# Own_21700_Board_v2_0_Final_AR.net
KiCad netlist of a schematic drawn in EAGLE
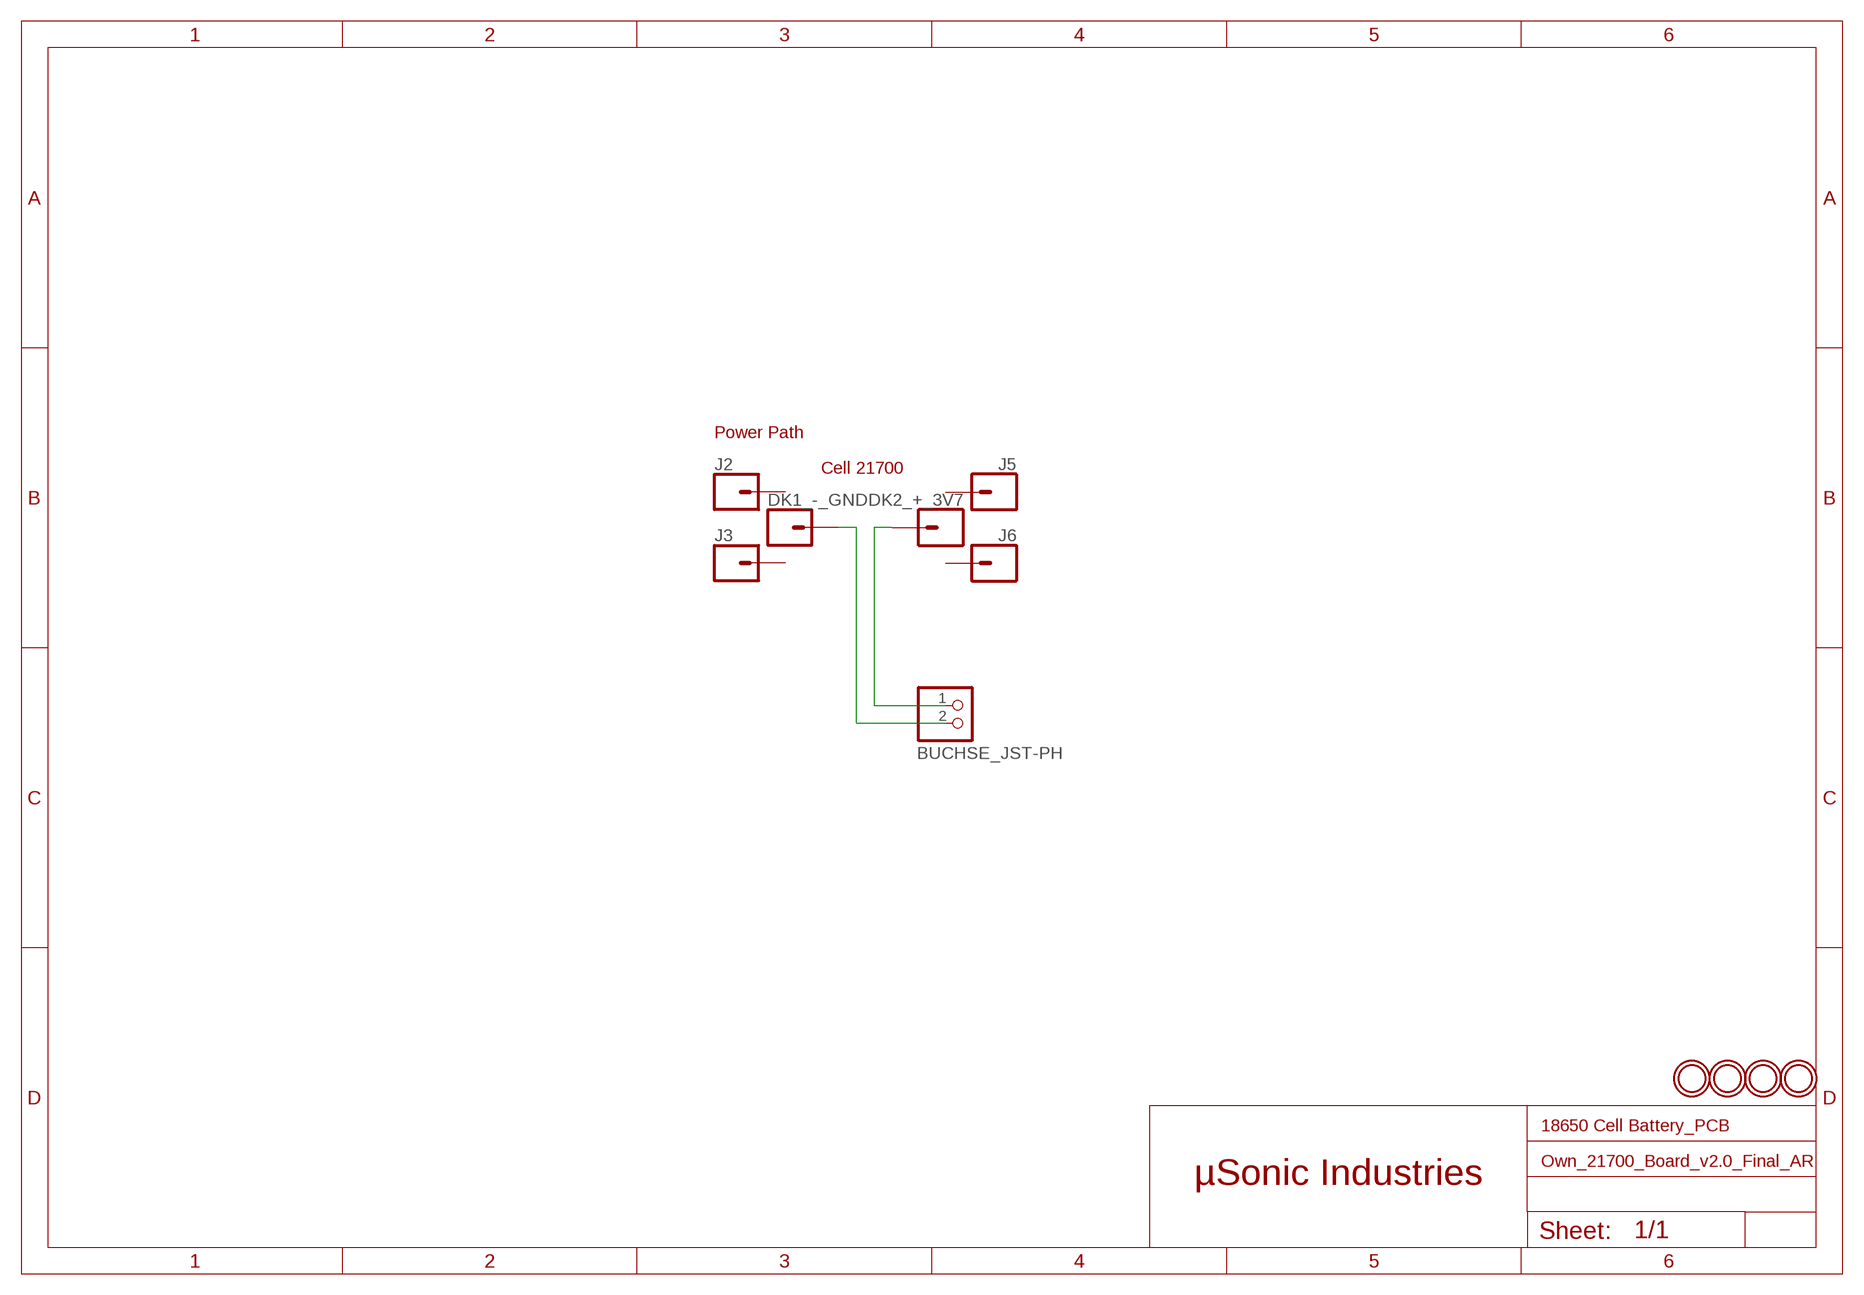
[diagram p0: schematic, sheet 1]

(export (version "E")
  (design (tool "Eeschema 10.0.6"))
  (components
    (comp (ref "BUCHSE_JST-PH")
      (value "JST_2PINOWN")
      (footprint "eagle-import:JST-PH-2-THMOWN")
      (libsource (lib "eagle-import") (part "JST_2PINOWN"))
    )
    (comp (ref "DK1_-_GND")
      (value "CONN_01PTH_2MM")
      (footprint "eagle-import:1X01_2MM")
      (libsource (lib "eagle-import") (part "CONN_01PTH_2MM"))
    )
    (comp (ref "DK2_+_3V7")
      (value "CONN_01PTH_2MM")
      (footprint "eagle-import:1X01_2MM")
      (libsource (lib "eagle-import") (part "CONN_01PTH_2MM"))
    )
    (comp (ref "J2")
      (value "CONN_01PTH_2MM")
      (footprint "eagle-import:1X01_2MM")
      (libsource (lib "eagle-import") (part "CONN_01PTH_2MM"))
    )
    (comp (ref "J3")
      (value "CONN_01PTH_2MM")
      (footprint "eagle-import:1X01_2MM")
      (libsource (lib "eagle-import") (part "CONN_01PTH_2MM"))
    )
    (comp (ref "J5")
      (value "CONN_01PTH_2MM")
      (footprint "eagle-import:1X01_2MM")
      (libsource (lib "eagle-import") (part "CONN_01PTH_2MM"))
    )
    (comp (ref "J6")
      (value "CONN_01PTH_2MM")
      (footprint "eagle-import:1X01_2MM")
      (libsource (lib "eagle-import") (part "CONN_01PTH_2MM"))
    )
    (comp (ref "U$1")
      (value "MOUNTINGHOLE2.5")
      (footprint "eagle-import:MOUNTINGHOLE_2.5_PLATED")
      (libsource (lib "eagle-import") (part "MOUNTINGHOLE2.5"))
    )
    (comp (ref "U$2")
      (value "MOUNTINGHOLE2.5")
      (footprint "eagle-import:MOUNTINGHOLE_2.5_PLATED")
      (libsource (lib "eagle-import") (part "MOUNTINGHOLE2.5"))
    )
    (comp (ref "U$3")
      (value "MOUNTINGHOLE2.5")
      (footprint "eagle-import:MOUNTINGHOLE_2.5_PLATED")
      (libsource (lib "eagle-import") (part "MOUNTINGHOLE2.5"))
    )
    (comp (ref "U$5")
      (value "MOUNTINGHOLE2.5")
      (footprint "eagle-import:MOUNTINGHOLE_2.5_PLATED")
      (libsource (lib "eagle-import") (part "MOUNTINGHOLE2.5"))
    )
  )
  (nets
    (net (code "1") (name "Net-(BUCHSE_JST-PH-1)") (class "Default")
      (node (ref "BUCHSE_JST-PH") (pin "2") (pinfunction "1_2") (pintype "passive"))
      (node (ref "DK1_-_GND") (pin "1") (pinfunction "1_1") (pintype "passive"))
    )
    (net (code "2") (name "Net-(BUCHSE_JST-PH-2)") (class "Default")
      (node (ref "BUCHSE_JST-PH") (pin "1") (pinfunction "2_1") (pintype "passive"))
      (node (ref "DK2_+_3V7") (pin "1") (pinfunction "1_1") (pintype "passive"))
    )
    (net (code "3") (name "unconnected-(J2-Pad1)") (class "Default")
      (node (ref "J2") (pin "1") (pinfunction "1_1") (pintype "passive"))
    )
    (net (code "4") (name "unconnected-(J3-Pad1)") (class "Default")
      (node (ref "J3") (pin "1") (pinfunction "1_1") (pintype "passive"))
    )
    (net (code "5") (name "unconnected-(J5-Pad1)") (class "Default")
      (node (ref "J5") (pin "1") (pinfunction "1_1") (pintype "passive"))
    )
    (net (code "6") (name "unconnected-(J6-Pad1)") (class "Default")
      (node (ref "J6") (pin "1") (pinfunction "1_1") (pintype "passive"))
    )
  )
)
